# AD597.net
KiCad netlist of a schematic drawn in EAGLE
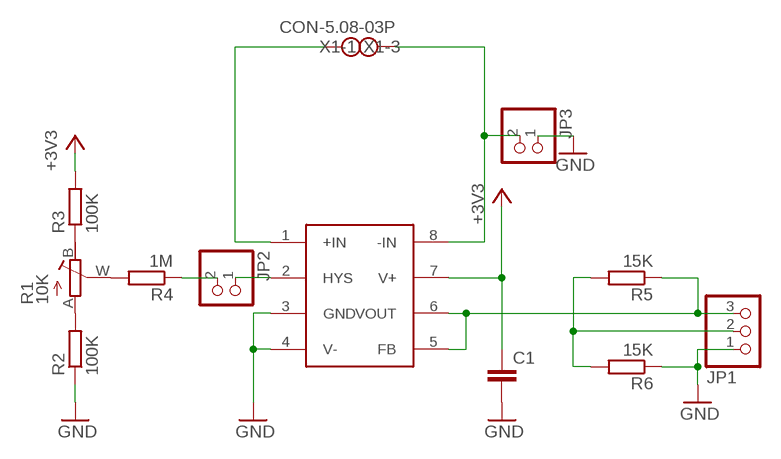
[diagram p0: schematic, sheet 1]

(export (version "E")
  (design (tool "Eeschema 10.0.6"))
  (components
    (comp (ref "C1")
      (value "CAP_0805")
      (footprint "eagle-import:C0805")
      (libsource (lib "eagle-import") (part "CAP_0805"))
    )
    (comp (ref "JP1")
      (value "PINHD-1X3/90")
      (footprint "eagle-import:1X03_90")
      (libsource (lib "eagle-import") (part "PINHD-1X3/90"))
    )
    (comp (ref "JP2")
      (value "PINHD-1X2")
      (footprint "eagle-import:1X02")
      (libsource (lib "eagle-import") (part "PINHD-1X2"))
    )
    (comp (ref "JP3")
      (value "PINHD-1X2")
      (footprint "eagle-import:1X02")
      (libsource (lib "eagle-import") (part "PINHD-1X2"))
    )
    (comp (ref "R1")
      (value "10K")
      (footprint "eagle-import:RJ9W")
      (libsource (lib "eagle-import") (part "R_POTTURN-X"))
    )
    (comp (ref "R2")
      (value "100K")
      (footprint "eagle-import:R0805")
      (libsource (lib "eagle-import") (part "R_0805"))
    )
    (comp (ref "R3")
      (value "100K")
      (footprint "eagle-import:R0805")
      (libsource (lib "eagle-import") (part "R_0805"))
    )
    (comp (ref "R4")
      (value "1M")
      (footprint "eagle-import:R0805")
      (libsource (lib "eagle-import") (part "R_0805"))
    )
    (comp (ref "R5")
      (value "15K")
      (footprint "eagle-import:R0805")
      (libsource (lib "eagle-import") (part "R_0805"))
    )
    (comp (ref "R6")
      (value "15K")
      (footprint "eagle-import:R0805")
      (libsource (lib "eagle-import") (part "R_0805"))
    )
    (comp (ref "U$1")
      (value "AD597ARZ")
      (footprint "eagle-import:SO8")
      (libsource (lib "eagle-import") (part "AD597ARZ"))
    )
    (comp (ref "X1")
      (value "CON-5.08-03P")
      (footprint "eagle-import:MKDSN1,5_3-5,08")
      (libsource (lib "eagle-import") (part "CON-5.08-03P"))
    )
  )
  (nets
    (net (code "1") (name "+3V3") (class "Default")
      (node (ref "C1") (pin "1") (pinfunction "1_1") (pintype "passive"))
      (node (ref "R3") (pin "2") (pinfunction "2_2") (pintype "passive"))
      (node (ref "U$1") (pin "7") (pinfunction "V+_7") (pintype "bidirectional"))
    )
    (net (code "2") (name "GND") (class "Default")
      (node (ref "C1") (pin "2") (pinfunction "2_2") (pintype "passive"))
      (node (ref "JP1") (pin "1") (pinfunction "1_1") (pintype "passive"))
      (node (ref "JP3") (pin "1") (pinfunction "1_1") (pintype "passive"))
      (node (ref "R2") (pin "1") (pinfunction "1_1") (pintype "passive"))
      (node (ref "R6") (pin "1") (pinfunction "1_1") (pintype "passive"))
      (node (ref "U$1") (pin "3") (pinfunction "GND_3") (pintype "bidirectional"))
      (node (ref "U$1") (pin "4") (pinfunction "V-_4") (pintype "bidirectional"))
    )
    (net (code "3") (name "Net-(JP1-Pad2)") (class "Default")
      (node (ref "JP1") (pin "2") (pinfunction "2_2") (pintype "passive"))
      (node (ref "R5") (pin "2") (pinfunction "2_2") (pintype "passive"))
      (node (ref "R6") (pin "2") (pinfunction "2_2") (pintype "passive"))
    )
    (net (code "4") (name "Net-(JP2-Pad2)") (class "Default")
      (node (ref "JP2") (pin "2") (pinfunction "2_2") (pintype "passive"))
      (node (ref "R4") (pin "1") (pinfunction "1_1") (pintype "passive"))
    )
    (net (code "5") (name "Net-(R1-E)") (class "Default")
      (node (ref "R1") (pin "B") (pinfunction "E_B") (pintype "passive"))
      (node (ref "R3") (pin "1") (pinfunction "1_1") (pintype "passive"))
    )
    (net (code "6") (name "Net-(R1-PadA)") (class "Default")
      (node (ref "R1") (pin "A") (pinfunction "A_A") (pintype "passive"))
      (node (ref "R2") (pin "2") (pinfunction "2_2") (pintype "passive"))
    )
    (net (code "7") (name "Net-(R1-S)") (class "Default")
      (node (ref "R1") (pin "W") (pinfunction "S_W") (pintype "passive"))
      (node (ref "R4") (pin "2") (pinfunction "2_2") (pintype "passive"))
    )
    (net (code "8") (name "Net-(U$1-+IN)") (class "Default")
      (node (ref "U$1") (pin "1") (pinfunction "+IN_1") (pintype "bidirectional"))
      (node (ref "X1") (pin "3") (pinfunction "KL_3") (pintype "passive"))
    )
    (net (code "9") (name "Net-(U$1--IN)") (class "Default")
      (node (ref "JP3") (pin "2") (pinfunction "2_2") (pintype "passive"))
      (node (ref "U$1") (pin "8") (pinfunction "-IN_8") (pintype "bidirectional"))
      (node (ref "X1") (pin "1") (pinfunction "KL_1") (pintype "passive"))
    )
    (net (code "10") (name "Net-(U$1-FB)") (class "Default")
      (node (ref "JP1") (pin "3") (pinfunction "3_3") (pintype "passive"))
      (node (ref "R5") (pin "1") (pinfunction "1_1") (pintype "passive"))
      (node (ref "U$1") (pin "5") (pinfunction "FB_5") (pintype "bidirectional"))
      (node (ref "U$1") (pin "6") (pinfunction "VOUT_6") (pintype "bidirectional"))
    )
    (net (code "11") (name "Net-(U$1-HYS)") (class "Default")
      (node (ref "JP2") (pin "1") (pinfunction "1_1") (pintype "passive"))
      (node (ref "U$1") (pin "2") (pinfunction "HYS_2") (pintype "bidirectional"))
    )
  )
)
